# ESP8266LEDBoard.net
KiCad netlist of a schematic drawn in EAGLE
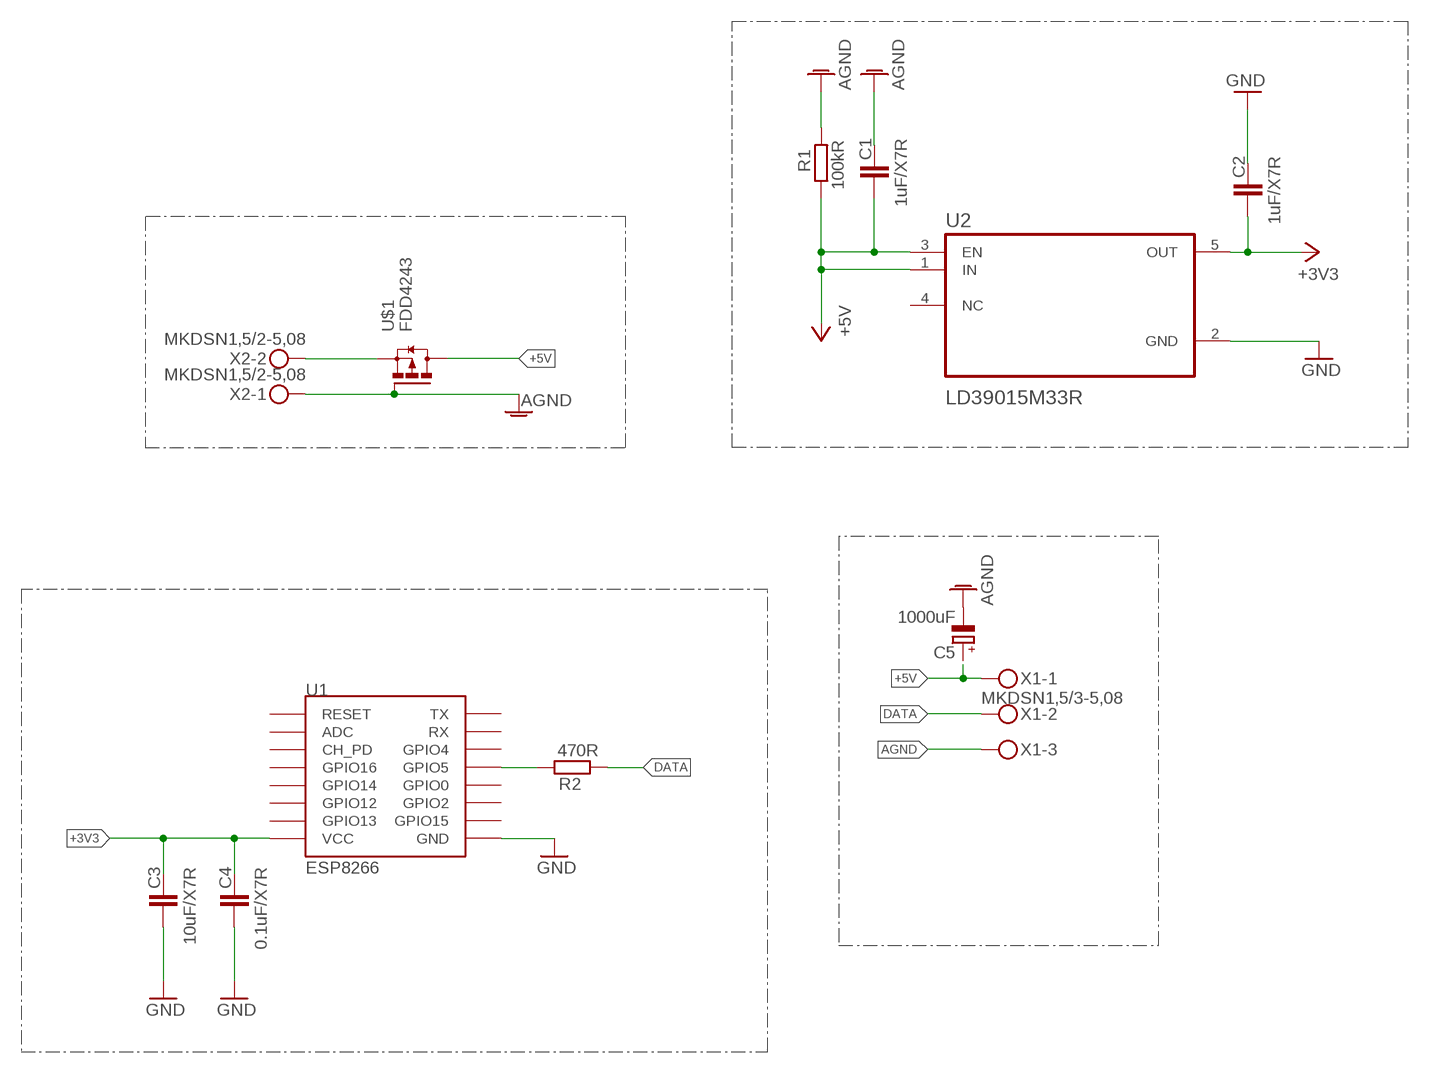
[diagram p0: schematic, sheet 1]

(export (version "E")
  (design (tool "Eeschema 10.0.6"))
  (components
    (comp (ref "C1")
      (value "1uF/X7R")
      (footprint "eagle-import:C0805")
      (libsource (lib "eagle-import") (part "C-EUC0805"))
    )
    (comp (ref "C2")
      (value "1uF/X7R")
      (footprint "eagle-import:C0805")
      (libsource (lib "eagle-import") (part "C-EUC0805"))
    )
    (comp (ref "C3")
      (value "10uF/X7R")
      (footprint "eagle-import:C0805")
      (libsource (lib "eagle-import") (part "C-EUC0805"))
    )
    (comp (ref "C4")
      (value "0.1uF/X7R")
      (footprint "eagle-import:C0805")
      (libsource (lib "eagle-import") (part "C-EUC0805"))
    )
    (comp (ref "C5")
      (value "1000uF")
      (footprint "eagle-import:UD-8X10_NICHICON")
      (libsource (lib "eagle-import") (part "CPOL-EUUD-8X10"))
    )
    (comp (ref "R1")
      (value "100kR")
      (footprint "eagle-import:R0805")
      (libsource (lib "eagle-import") (part "R-EU_R0805"))
    )
    (comp (ref "R2")
      (value "470R")
      (footprint "eagle-import:R0805")
      (libsource (lib "eagle-import") (part "R-EU_R0805"))
    )
    (comp (ref "U$1")
      (value "FDD4243")
      (footprint "eagle-import:TO252")
      (fields (field (name "MF") "ON Semiconductor"))
      (libsource (lib "eagle-import") (part "FDD4243"))
    )
    (comp (ref "U1")
      (value "ESP8266")
      (footprint "eagle-import:ESP12-SMD")
      (libsource (lib "eagle-import") (part "ESP12SMD"))
    )
    (comp (ref "U2")
      (value "LD39015M33R")
      (footprint "eagle-import:SOT95P280X145-5N")
      (fields (field (name "MF") "STMicroelectronics"))
      (libsource (lib "eagle-import") (part "LD39015M33R"))
    )
    (comp (ref "X1")
      (value "MKDSN1,5/3-5,08")
      (footprint "eagle-import:MKDSN1,5_3-5,08")
      (libsource (lib "eagle-import") (part "MKDSN1,5/3-5,08"))
    )
    (comp (ref "X2")
      (value "MKDSN1,5/2-5,08")
      (footprint "eagle-import:MKDSN1,5_2-5,08")
      (libsource (lib "eagle-import") (part "MKDSN1,5/2-5,08"))
    )
  )
  (nets
    (net (code "1") (name "+3V3") (class "Default")
      (node (ref "C2") (pin "1") (pinfunction "1_1") (pintype "passive"))
      (node (ref "C3") (pin "2") (pinfunction "2_2") (pintype "passive"))
      (node (ref "C4") (pin "2") (pinfunction "2_2") (pintype "passive"))
      (node (ref "U1") (pin "VCC") (pinfunction "VCC_VCC") (pintype "bidirectional"))
      (node (ref "U2") (pin "5") (pinfunction "OUT_5") (pintype "output"))
    )
    (net (code "2") (name "+5V") (class "Default")
      (node (ref "C1") (pin "1") (pinfunction "1_1") (pintype "passive"))
      (node (ref "C5") (pin "+") (pinfunction "+_+") (pintype "passive"))
      (node (ref "R1") (pin "1") (pinfunction "1_1") (pintype "passive"))
      (node (ref "U$1") (pin "3") (pinfunction "D_3") (pintype "passive"))
      (node (ref "U2") (pin "1") (pinfunction "IN_1") (pintype "input"))
      (node (ref "U2") (pin "3") (pinfunction "EN_3") (pintype "input"))
      (node (ref "X1") (pin "1") (pinfunction "KL_1") (pintype "passive"))
    )
    (net (code "3") (name "AGND") (class "Default")
      (node (ref "C1") (pin "2") (pinfunction "2_2") (pintype "passive"))
      (node (ref "C5") (pin "-") (pinfunction "-_-") (pintype "passive"))
      (node (ref "R1") (pin "2") (pinfunction "2_2") (pintype "passive"))
      (node (ref "U$1") (pin "1") (pinfunction "G_1") (pintype "passive"))
      (node (ref "X1") (pin "3") (pinfunction "KL_3") (pintype "passive"))
      (node (ref "X2") (pin "1") (pinfunction "KL_1") (pintype "passive"))
    )
    (net (code "4") (name "DATA") (class "Default")
      (node (ref "R2") (pin "1") (pinfunction "1_1") (pintype "passive"))
      (node (ref "X1") (pin "2") (pinfunction "KL_2") (pintype "passive"))
    )
    (net (code "5") (name "GND") (class "Default")
      (node (ref "C2") (pin "2") (pinfunction "2_2") (pintype "passive"))
      (node (ref "C3") (pin "1") (pinfunction "1_1") (pintype "passive"))
      (node (ref "C4") (pin "1") (pinfunction "1_1") (pintype "passive"))
      (node (ref "U1") (pin "GND") (pinfunction "GND_GND") (pintype "bidirectional"))
      (node (ref "U2") (pin "2") (pinfunction "GND_2") (pintype "power_in"))
    )
    (net (code "6") (name "Net-(R2-Pad2)") (class "Default")
      (node (ref "R2") (pin "2") (pinfunction "2_2") (pintype "passive"))
      (node (ref "U1") (pin "GPIO5") (pinfunction "GPIO5_GPIO5") (pintype "bidirectional"))
    )
    (net (code "7") (name "Net-(U$1-S)") (class "Default")
      (node (ref "U$1") (pin "2") (pinfunction "S_2") (pintype "passive"))
      (node (ref "X2") (pin "2") (pinfunction "KL_2") (pintype "passive"))
    )
    (net (code "8") (name "unconnected-(U1-PadADC)") (class "Default")
      (node (ref "U1") (pin "ADC") (pinfunction "ADC_ADC") (pintype "bidirectional"))
    )
    (net (code "9") (name "unconnected-(U1-PadCH_PD)") (class "Default")
      (node (ref "U1") (pin "CH_PD") (pinfunction "CH_PD_CH_PD") (pintype "bidirectional"))
    )
    (net (code "10") (name "unconnected-(U1-PadGPIO0)") (class "Default")
      (node (ref "U1") (pin "GPIO0") (pinfunction "GPIO0_GPIO0") (pintype "bidirectional"))
    )
    (net (code "11") (name "unconnected-(U1-PadGPIO2)") (class "Default")
      (node (ref "U1") (pin "GPIO2") (pinfunction "GPIO2_GPIO2") (pintype "bidirectional"))
    )
    (net (code "12") (name "unconnected-(U1-PadGPIO4)") (class "Default")
      (node (ref "U1") (pin "GPIO4") (pinfunction "GPIO4_GPIO4") (pintype "bidirectional"))
    )
    (net (code "13") (name "unconnected-(U1-PadGPIO12)") (class "Default")
      (node (ref "U1") (pin "GPIO12") (pinfunction "GPIO12_GPIO12") (pintype "bidirectional"))
    )
    (net (code "14") (name "unconnected-(U1-PadGPIO13)") (class "Default")
      (node (ref "U1") (pin "GPIO13") (pinfunction "GPIO13_GPIO13") (pintype "bidirectional"))
    )
    (net (code "15") (name "unconnected-(U1-PadGPIO14)") (class "Default")
      (node (ref "U1") (pin "GPIO14") (pinfunction "GPIO14_GPIO14") (pintype "bidirectional"))
    )
    (net (code "16") (name "unconnected-(U1-PadGPIO15)") (class "Default")
      (node (ref "U1") (pin "GPIO15") (pinfunction "GPIO15_GPIO15") (pintype "bidirectional"))
    )
    (net (code "17") (name "unconnected-(U1-PadGPIO16)") (class "Default")
      (node (ref "U1") (pin "GPIO16") (pinfunction "GPIO16_GPIO16") (pintype "bidirectional"))
    )
    (net (code "18") (name "unconnected-(U1-PadRESET)") (class "Default")
      (node (ref "U1") (pin "RESET") (pinfunction "RESET_RESET") (pintype "bidirectional"))
    )
    (net (code "19") (name "unconnected-(U1-RX-PadRXD0)") (class "Default")
      (node (ref "U1") (pin "RXD0") (pinfunction "RX_RXD0") (pintype "bidirectional"))
    )
    (net (code "20") (name "unconnected-(U1-TX-PadTXD0)") (class "Default")
      (node (ref "U1") (pin "TXD0") (pinfunction "TX_TXD0") (pintype "bidirectional"))
    )
    (net (code "21") (name "unconnected-(U2-NC-Pad4)") (class "Default")
      (node (ref "U2") (pin "4") (pinfunction "NC_4") (pintype "bidirectional"))
    )
  )
)
